# S_H.net
KiCad netlist of a schematic drawn in Altium Designer
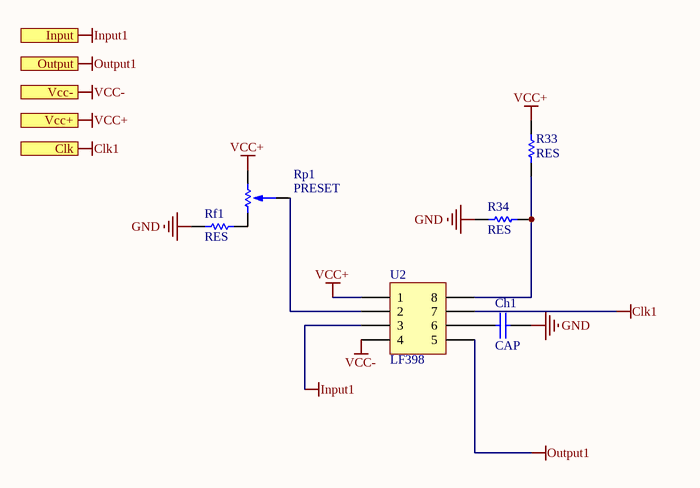
[diagram p0: S&H.SchDoc]

(export (version "E")
  (design (tool "Eeschema 10.0.6"))
  (components
    (comp (ref "Ch1") (value "CAP") (footprint "0805") (libsource (lib "Schematics") (part "CAP")))
    (comp (ref "R33") (value "RES") (footprint "0805") (libsource (lib "LIBEBAL") (part "RES")))
    (comp (ref "R34") (value "RES") (footprint "0805") (libsource (lib "LIBEBAL") (part "RES")))
    (comp (ref "Rf1") (value "RES") (footprint "0805") (libsource (lib "Schematics") (part "RES")))
    (comp (ref "Rp1") (value "PRESET") (footprint "PRESET V") (libsource (lib "Schematics") (part "PRESET")))
    (comp (ref "U2") (value "LF398") (footprint "DIP8") (libsource (lib "Schematics") (part "IC_DIP8")))
  )
  (nets
    (net (code "1") (name "Clk1") (class "Default")
      (node (ref "U2") (pin "7") (pinfunction "7_7") (pintype "passive"))
    )
    (net (code "2") (name "GND") (class "Default")
      (node (ref "Ch1") (pin "2") (pinfunction "2_2") (pintype "passive"))
      (node (ref "R34") (pin "1") (pinfunction "1_1") (pintype "passive"))
      (node (ref "Rf1") (pin "1") (pinfunction "1_1") (pintype "passive"))
    )
    (net (code "3") (name "Input1") (class "Default")
      (node (ref "U2") (pin "3") (pinfunction "3_3") (pintype "passive"))
    )
    (net (code "4") (name "Net-(Ch1-Pad1)") (class "Default")
      (node (ref "Ch1") (pin "1") (pinfunction "1_1") (pintype "passive"))
      (node (ref "U2") (pin "6") (pinfunction "6_6") (pintype "passive"))
    )
    (net (code "5") (name "Net-(R33-Pad1)") (class "Default")
      (node (ref "R33") (pin "1") (pinfunction "1_1") (pintype "passive"))
      (node (ref "R34") (pin "2") (pinfunction "2_2") (pintype "passive"))
      (node (ref "U2") (pin "8") (pinfunction "8_8") (pintype "passive"))
    )
    (net (code "6") (name "Net-(Rf1-Pad2)") (class "Default")
      (node (ref "Rf1") (pin "2") (pinfunction "2_2") (pintype "passive"))
      (node (ref "Rp1") (pin "3") (pinfunction "3_3") (pintype "passive"))
    )
    (net (code "7") (name "Net-(Rp1-Pad2)") (class "Default")
      (node (ref "Rp1") (pin "2") (pinfunction "2_2") (pintype "passive"))
      (node (ref "U2") (pin "2") (pinfunction "2_2") (pintype "passive"))
    )
    (net (code "8") (name "Output1") (class "Default")
      (node (ref "U2") (pin "5") (pinfunction "5_5") (pintype "passive"))
    )
    (net (code "9") (name "VCC+") (class "Default")
      (node (ref "R33") (pin "2") (pinfunction "2_2") (pintype "passive"))
      (node (ref "Rp1") (pin "1") (pinfunction "1_1") (pintype "passive"))
      (node (ref "U2") (pin "1") (pinfunction "1_1") (pintype "passive"))
    )
    (net (code "10") (name "VCC-") (class "Default")
      (node (ref "U2") (pin "4") (pinfunction "4_4") (pintype "passive"))
    )
  )
)
